# pyboard2.net
KiCad netlist of a schematic drawn in EAGLE
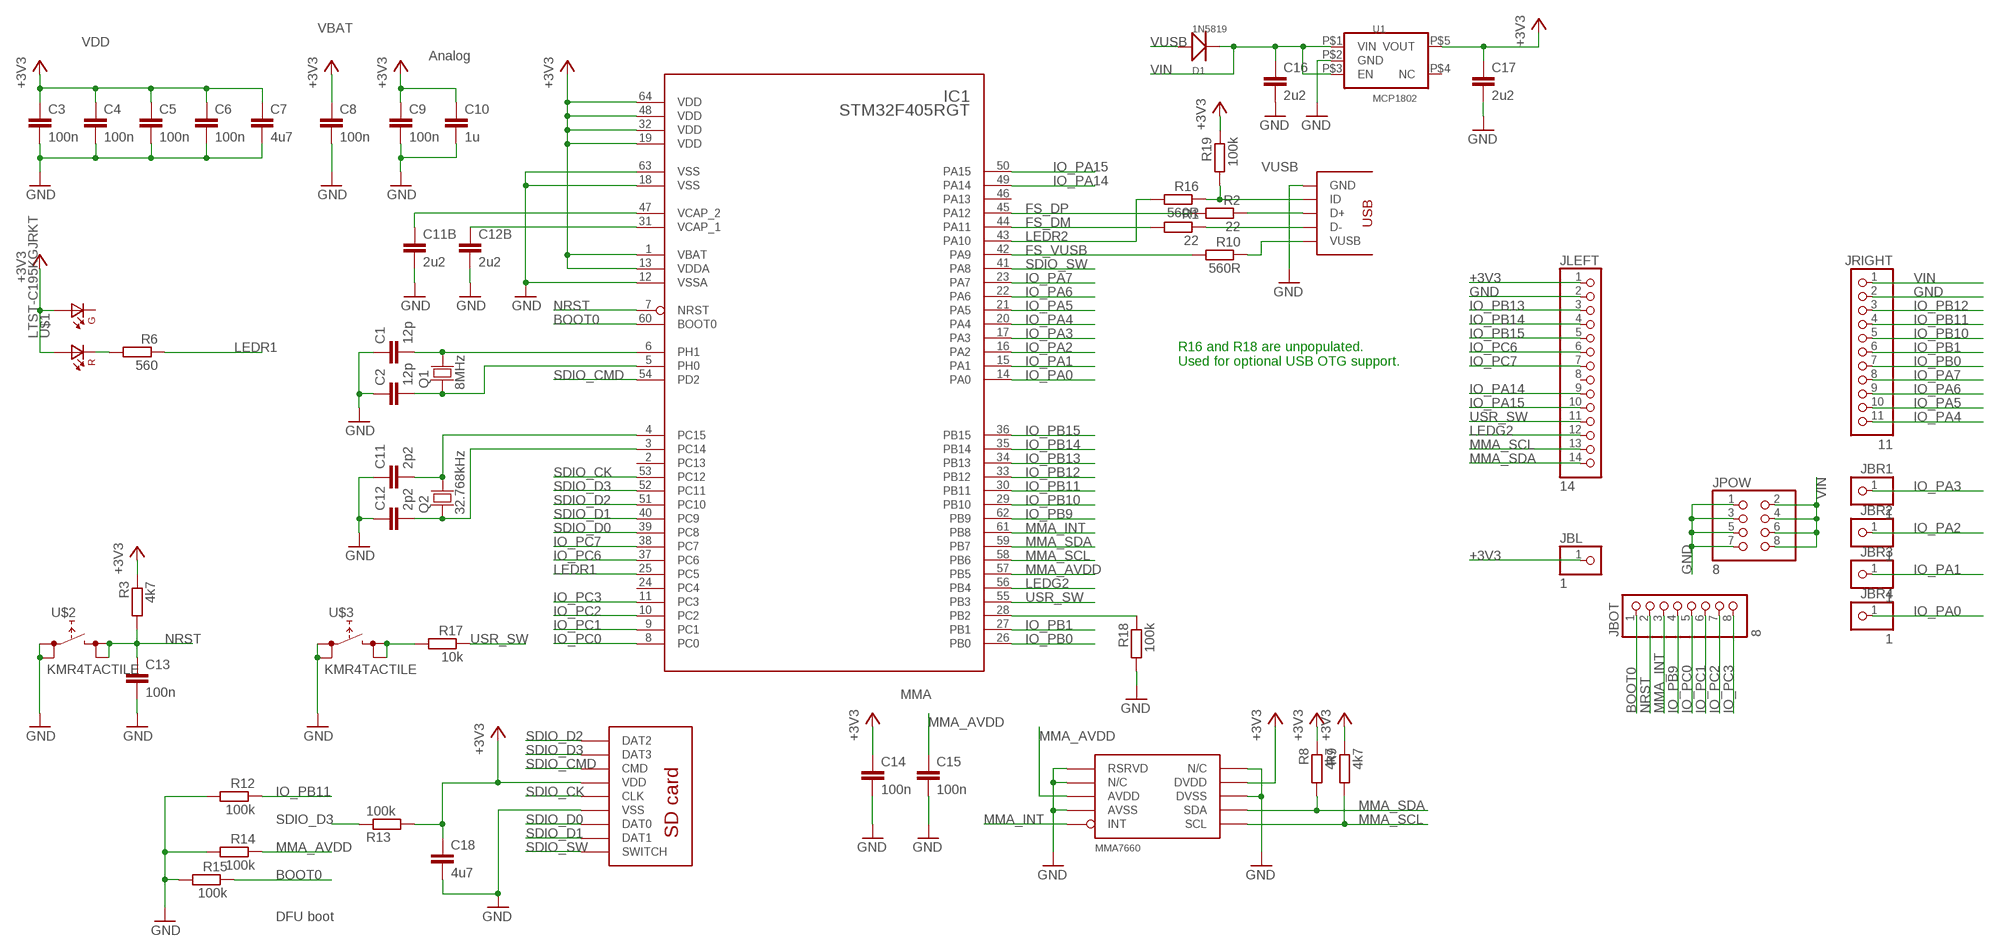
[diagram p0: schematic, sheet 1]

(export (version "E")
  (design (tool "Eeschema 10.0.6"))
  (components
    (comp (ref "C1")
      (value "12p")
      (footprint "eagle-import:C0603")
      (libsource (lib "eagle-import") (part "C-EUC0603"))
    )
    (comp (ref "C2")
      (value "12p")
      (footprint "eagle-import:C0603")
      (libsource (lib "eagle-import") (part "C-EUC0603"))
    )
    (comp (ref "C3")
      (value "100n")
      (footprint "eagle-import:C0603")
      (libsource (lib "eagle-import") (part "C-EUC0603"))
    )
    (comp (ref "C4")
      (value "100n")
      (footprint "eagle-import:C0603")
      (libsource (lib "eagle-import") (part "C-EUC0603"))
    )
    (comp (ref "C5")
      (value "100n")
      (footprint "eagle-import:C0603")
      (libsource (lib "eagle-import") (part "C-EUC0603"))
    )
    (comp (ref "C6")
      (value "100n")
      (footprint "eagle-import:C0603")
      (libsource (lib "eagle-import") (part "C-EUC0603"))
    )
    (comp (ref "C7")
      (value "4u7")
      (footprint "eagle-import:C0603")
      (libsource (lib "eagle-import") (part "C-EUC0603"))
    )
    (comp (ref "C8")
      (value "100n")
      (footprint "eagle-import:C0603")
      (libsource (lib "eagle-import") (part "C-EUC0603"))
    )
    (comp (ref "C9")
      (value "100n")
      (footprint "eagle-import:C0603")
      (libsource (lib "eagle-import") (part "C-EUC0603"))
    )
    (comp (ref "C10")
      (value "1u")
      (footprint "eagle-import:C0603")
      (libsource (lib "eagle-import") (part "C-EUC0603"))
    )
    (comp (ref "C11")
      (value "2p2")
      (footprint "eagle-import:C0603")
      (libsource (lib "eagle-import") (part "C-EUC0603"))
    )
    (comp (ref "C11B")
      (value "2u2")
      (footprint "eagle-import:C0603")
      (libsource (lib "eagle-import") (part "C-EUC0603"))
    )
    (comp (ref "C12")
      (value "2p2")
      (footprint "eagle-import:C0603")
      (libsource (lib "eagle-import") (part "C-EUC0603"))
    )
    (comp (ref "C12B")
      (value "2u2")
      (footprint "eagle-import:C0603")
      (libsource (lib "eagle-import") (part "C-EUC0603"))
    )
    (comp (ref "C13")
      (value "100n")
      (footprint "eagle-import:C0603")
      (libsource (lib "eagle-import") (part "C-EUC0603"))
    )
    (comp (ref "C14")
      (value "100n")
      (footprint "eagle-import:C0603")
      (libsource (lib "eagle-import") (part "C-EUC0603"))
    )
    (comp (ref "C15")
      (value "100n")
      (footprint "eagle-import:C0603")
      (libsource (lib "eagle-import") (part "C-EUC0603"))
    )
    (comp (ref "C16")
      (value "2u2")
      (footprint "eagle-import:C0603")
      (libsource (lib "eagle-import") (part "C-EUC0603"))
    )
    (comp (ref "C17")
      (value "2u2")
      (footprint "eagle-import:C0603")
      (libsource (lib "eagle-import") (part "C-EUC0603"))
    )
    (comp (ref "C18")
      (value "4u7")
      (footprint "eagle-import:C0603")
      (libsource (lib "eagle-import") (part "C-EUC0603"))
    )
    (comp (ref "D1")
      (value "1N5819")
      (footprint "eagle-import:SOD-123")
      (libsource (lib "eagle-import") (part "1N5819"))
    )
    (comp (ref "IC1")
      (value "STM32F405RGT")
      (footprint "eagle-import:LQFP64")
      (libsource (lib "eagle-import") (part "STM32F405RTG"))
    )
    (comp (ref "JBL")
      (value "1")
      (footprint "eagle-import:1X01")
      (libsource (lib "eagle-import") (part "PINHD-1X1"))
    )
    (comp (ref "JBOT")
      (value "8")
      (footprint "eagle-import:1X08")
      (libsource (lib "eagle-import") (part "PINHD-1X8"))
    )
    (comp (ref "JBR1")
      (value "1")
      (footprint "eagle-import:1X01")
      (libsource (lib "eagle-import") (part "PINHD-1X1"))
    )
    (comp (ref "JBR2")
      (value "1")
      (footprint "eagle-import:1X01")
      (libsource (lib "eagle-import") (part "PINHD-1X1"))
    )
    (comp (ref "JBR3")
      (value "1")
      (footprint "eagle-import:1X01")
      (libsource (lib "eagle-import") (part "PINHD-1X1"))
    )
    (comp (ref "JBR4")
      (value "1")
      (footprint "eagle-import:1X01")
      (libsource (lib "eagle-import") (part "PINHD-1X1"))
    )
    (comp (ref "JLEFT")
      (value "14")
      (footprint "eagle-import:1X14")
      (libsource (lib "eagle-import") (part "PINHD-1X14"))
    )
    (comp (ref "JPOW")
      (value "8")
      (footprint "eagle-import:2X04")
      (libsource (lib "eagle-import") (part "PINHD-2X4"))
    )
    (comp (ref "JRIGHT")
      (value "11")
      (footprint "eagle-import:1X11")
      (libsource (lib "eagle-import") (part "PINHD-1X11"))
    )
    (comp (ref "Q1")
      (value "8MHz")
      (footprint "eagle-import:TXC-SMD-50X32")
      (libsource (lib "eagle-import") (part "TXC-CRYSTAL50X32"))
    )
    (comp (ref "Q2")
      (value "32.768kHz")
      (footprint "eagle-import:TXC-SMD-32X15")
      (libsource (lib "eagle-import") (part "TXC-CRYSTAL32X15"))
    )
    (comp (ref "R1")
      (value "22")
      (footprint "eagle-import:R0603")
      (libsource (lib "eagle-import") (part "R-EU_R0603"))
    )
    (comp (ref "R2")
      (value "22")
      (footprint "eagle-import:R0603")
      (libsource (lib "eagle-import") (part "R-EU_R0603"))
    )
    (comp (ref "R3")
      (value "4k7")
      (footprint "eagle-import:R0603")
      (libsource (lib "eagle-import") (part "R-EU_R0603"))
    )
    (comp (ref "R6")
      (value "560")
      (footprint "eagle-import:R0603")
      (libsource (lib "eagle-import") (part "R-EU_R0603"))
    )
    (comp (ref "R8")
      (value "4k7")
      (footprint "eagle-import:R0603")
      (libsource (lib "eagle-import") (part "R-EU_R0603"))
    )
    (comp (ref "R9")
      (value "4k7")
      (footprint "eagle-import:R0603")
      (libsource (lib "eagle-import") (part "R-EU_R0603"))
    )
    (comp (ref "R10")
      (value "560R")
      (footprint "eagle-import:R0603")
      (libsource (lib "eagle-import") (part "R-EU_R0603"))
    )
    (comp (ref "R12")
      (value "100k")
      (footprint "eagle-import:R0603")
      (libsource (lib "eagle-import") (part "R-EU_R0603"))
    )
    (comp (ref "R13")
      (value "100k")
      (footprint "eagle-import:R0603")
      (libsource (lib "eagle-import") (part "R-EU_R0603"))
    )
    (comp (ref "R14")
      (value "100k")
      (footprint "eagle-import:R0603")
      (libsource (lib "eagle-import") (part "R-EU_R0603"))
    )
    (comp (ref "R15")
      (value "100k")
      (footprint "eagle-import:R0603")
      (libsource (lib "eagle-import") (part "R-EU_R0603"))
    )
    (comp (ref "R16")
      (value "560R")
      (footprint "eagle-import:R0603")
      (libsource (lib "eagle-import") (part "R-EU_R0603"))
    )
    (comp (ref "R17")
      (value "10k")
      (footprint "eagle-import:R0603")
      (libsource (lib "eagle-import") (part "R-EU_R0603"))
    )
    (comp (ref "R18")
      (value "100k")
      (footprint "eagle-import:R0603")
      (libsource (lib "eagle-import") (part "R-EU_R0603"))
    )
    (comp (ref "R19")
      (value "100k")
      (footprint "eagle-import:R0603")
      (libsource (lib "eagle-import") (part "R-EU_R0603"))
    )
    (comp (ref "U$1")
      (value "LTST-C195KGJRKT")
      (footprint "eagle-import:LTST-BILED-15X16")
      (libsource (lib "eagle-import") (part "LTST-C195KGJRKT"))
    )
    (comp (ref "U$2")
      (value "KMR4TACTILE")
      (footprint "eagle-import:KMR4SWITCH")
      (libsource (lib "eagle-import") (part "KMR4TACTILE"))
    )
    (comp (ref "U$3")
      (value "KMR4TACTILE")
      (footprint "eagle-import:KMR4SWITCH")
      (libsource (lib "eagle-import") (part "KMR4TACTILE"))
    )
    (comp (ref "U$4")
      (value "MOLEX-SD-105027")
      (footprint "eagle-import:MOLEX-SD-105027-PKG")
      (libsource (lib "eagle-import") (part "MOLEX-SD-105027"))
    )
    (comp (ref "U$5")
      (value "MMA7660")
      (footprint "eagle-import:DFN10")
      (libsource (lib "eagle-import") (part "MMA7660"))
    )
    (comp (ref "U$7")
      (value "USB-MICRO-AB")
      (footprint "eagle-import:HRS-USB-ZX62D-AB-5P8-PKG")
      (libsource (lib "eagle-import") (part "USB-MICRO-AB"))
    )
    (comp (ref "U1")
      (value "MCP1802")
      (footprint "eagle-import:SOT-23-5")
      (libsource (lib "eagle-import") (part "MCP1802"))
    )
  )
  (nets
    (net (code "1") (name "+3V3") (class "Default")
      (node (ref "C10") (pin "1") (pinfunction "1_1") (pintype "passive"))
      (node (ref "C14") (pin "1") (pinfunction "1_1") (pintype "passive"))
      (node (ref "C17") (pin "1") (pinfunction "1_1") (pintype "passive"))
      (node (ref "C18") (pin "1") (pinfunction "1_1") (pintype "passive"))
      (node (ref "C3") (pin "1") (pinfunction "1_1") (pintype "passive"))
      (node (ref "C4") (pin "1") (pinfunction "1_1") (pintype "passive"))
      (node (ref "C5") (pin "1") (pinfunction "1_1") (pintype "passive"))
      (node (ref "C6") (pin "1") (pinfunction "1_1") (pintype "passive"))
      (node (ref "C7") (pin "1") (pinfunction "1_1") (pintype "passive"))
      (node (ref "C8") (pin "1") (pinfunction "1_1") (pintype "passive"))
      (node (ref "C9") (pin "1") (pinfunction "1_1") (pintype "passive"))
      (node (ref "IC1") (pin "1") (pinfunction "VBAT_1") (pintype "power_in"))
      (node (ref "IC1") (pin "13") (pinfunction "VDDA_13") (pintype "power_in"))
      (node (ref "IC1") (pin "19") (pinfunction "VDD_19") (pintype "power_in"))
      (node (ref "IC1") (pin "32") (pinfunction "VDD_32") (pintype "power_in"))
      (node (ref "IC1") (pin "48") (pinfunction "VDD_48") (pintype "power_in"))
      (node (ref "IC1") (pin "64") (pinfunction "VDD_64") (pintype "power_in"))
      (node (ref "JBL") (pin "1") (pinfunction "1_1") (pintype "passive"))
      (node (ref "JLEFT") (pin "1") (pinfunction "1_1") (pintype "passive"))
      (node (ref "R13") (pin "2") (pinfunction "2_2") (pintype "passive"))
      (node (ref "R19") (pin "1") (pinfunction "1_1") (pintype "passive"))
      (node (ref "R3") (pin "1") (pinfunction "1_1") (pintype "passive"))
      (node (ref "R8") (pin "1") (pinfunction "1_1") (pintype "passive"))
      (node (ref "R9") (pin "1") (pinfunction "1_1") (pintype "passive"))
      (node (ref "U$1") (pin "P$1") (pinfunction "A1_P$1") (pintype "passive"))
      (node (ref "U$1") (pin "P$2") (pinfunction "A2_P$2") (pintype "passive"))
      (node (ref "U$4") (pin "P$4") (pinfunction "VDD_P$4") (pintype "bidirectional"))
      (node (ref "U$5") (pin "P$9") (pinfunction "DVDD_P$9") (pintype "power_in"))
      (node (ref "U1") (pin "P$5") (pinfunction "VOUT_P$5") (pintype "power_in"))
    )
    (net (code "2") (name "/BOOT0") (class "Default")
      (node (ref "IC1") (pin "60") (pinfunction "BOOT0_60") (pintype "bidirectional"))
      (node (ref "JBOT") (pin "1") (pinfunction "1_1") (pintype "passive"))
      (node (ref "R15") (pin "1") (pinfunction "1_1") (pintype "passive"))
    )
    (net (code "3") (name "/FS_DM") (class "Default")
      (node (ref "IC1") (pin "44") (pinfunction "PA11_44") (pintype "bidirectional"))
      (node (ref "R1") (pin "2") (pinfunction "2_2") (pintype "passive"))
    )
    (net (code "4") (name "/FS_DP") (class "Default")
      (node (ref "IC1") (pin "45") (pinfunction "PA12_45") (pintype "bidirectional"))
      (node (ref "R2") (pin "2") (pinfunction "2_2") (pintype "passive"))
    )
    (net (code "5") (name "/FS_VUSB") (class "Default")
      (node (ref "IC1") (pin "42") (pinfunction "PA9_42") (pintype "bidirectional"))
      (node (ref "R10") (pin "2") (pinfunction "2_2") (pintype "passive"))
    )
    (net (code "6") (name "/IO_PA0") (class "Default")
      (node (ref "IC1") (pin "14") (pinfunction "PA0_14") (pintype "bidirectional"))
      (node (ref "JBR4") (pin "1") (pinfunction "1_1") (pintype "passive"))
    )
    (net (code "7") (name "/IO_PA1") (class "Default")
      (node (ref "IC1") (pin "15") (pinfunction "PA1_15") (pintype "bidirectional"))
      (node (ref "JBR3") (pin "1") (pinfunction "1_1") (pintype "passive"))
    )
    (net (code "8") (name "/IO_PA2") (class "Default")
      (node (ref "IC1") (pin "16") (pinfunction "PA2_16") (pintype "bidirectional"))
      (node (ref "JBR2") (pin "1") (pinfunction "1_1") (pintype "passive"))
    )
    (net (code "9") (name "/IO_PA3") (class "Default")
      (node (ref "IC1") (pin "17") (pinfunction "PA3_17") (pintype "bidirectional"))
      (node (ref "JBR1") (pin "1") (pinfunction "1_1") (pintype "passive"))
    )
    (net (code "10") (name "/IO_PA4") (class "Default")
      (node (ref "IC1") (pin "20") (pinfunction "PA4_20") (pintype "bidirectional"))
      (node (ref "JRIGHT") (pin "11") (pinfunction "11_11") (pintype "passive"))
    )
    (net (code "11") (name "/IO_PA5") (class "Default")
      (node (ref "IC1") (pin "21") (pinfunction "PA5_21") (pintype "bidirectional"))
      (node (ref "JRIGHT") (pin "10") (pinfunction "10_10") (pintype "passive"))
    )
    (net (code "12") (name "/IO_PA6") (class "Default")
      (node (ref "IC1") (pin "22") (pinfunction "PA6_22") (pintype "bidirectional"))
      (node (ref "JRIGHT") (pin "9") (pinfunction "9_9") (pintype "passive"))
    )
    (net (code "13") (name "/IO_PA7") (class "Default")
      (node (ref "IC1") (pin "23") (pinfunction "PA7_23") (pintype "bidirectional"))
      (node (ref "JRIGHT") (pin "8") (pinfunction "8_8") (pintype "passive"))
    )
    (net (code "14") (name "/IO_PA14") (class "Default")
      (node (ref "IC1") (pin "49") (pinfunction "PA14_49") (pintype "bidirectional"))
      (node (ref "JLEFT") (pin "9") (pinfunction "9_9") (pintype "passive"))
    )
    (net (code "15") (name "/IO_PA15") (class "Default")
      (node (ref "IC1") (pin "50") (pinfunction "PA15_50") (pintype "bidirectional"))
      (node (ref "JLEFT") (pin "10") (pinfunction "10_10") (pintype "passive"))
    )
    (net (code "16") (name "/IO_PB0") (class "Default")
      (node (ref "IC1") (pin "26") (pinfunction "PB0_26") (pintype "bidirectional"))
      (node (ref "JRIGHT") (pin "7") (pinfunction "7_7") (pintype "passive"))
    )
    (net (code "17") (name "/IO_PB1") (class "Default")
      (node (ref "IC1") (pin "27") (pinfunction "PB1_27") (pintype "bidirectional"))
      (node (ref "JRIGHT") (pin "6") (pinfunction "6_6") (pintype "passive"))
    )
    (net (code "18") (name "/IO_PB9") (class "Default")
      (node (ref "IC1") (pin "62") (pinfunction "PB9_62") (pintype "bidirectional"))
      (node (ref "JBOT") (pin "4") (pinfunction "4_4") (pintype "passive"))
    )
    (net (code "19") (name "/IO_PB10") (class "Default")
      (node (ref "IC1") (pin "29") (pinfunction "PB10_29") (pintype "bidirectional"))
      (node (ref "JRIGHT") (pin "5") (pinfunction "5_5") (pintype "passive"))
    )
    (net (code "20") (name "/IO_PB11") (class "Default")
      (node (ref "IC1") (pin "30") (pinfunction "PB11_30") (pintype "bidirectional"))
      (node (ref "JRIGHT") (pin "4") (pinfunction "4_4") (pintype "passive"))
      (node (ref "R12") (pin "1") (pinfunction "1_1") (pintype "passive"))
    )
    (net (code "21") (name "/IO_PB12") (class "Default")
      (node (ref "IC1") (pin "33") (pinfunction "PB12_33") (pintype "bidirectional"))
      (node (ref "JRIGHT") (pin "3") (pinfunction "3_3") (pintype "passive"))
    )
    (net (code "22") (name "/IO_PB13") (class "Default")
      (node (ref "IC1") (pin "34") (pinfunction "PB13_34") (pintype "bidirectional"))
      (node (ref "JLEFT") (pin "3") (pinfunction "3_3") (pintype "passive"))
    )
    (net (code "23") (name "/IO_PB14") (class "Default")
      (node (ref "IC1") (pin "35") (pinfunction "PB14_35") (pintype "bidirectional"))
      (node (ref "JLEFT") (pin "4") (pinfunction "4_4") (pintype "passive"))
    )
    (net (code "24") (name "/IO_PB15") (class "Default")
      (node (ref "IC1") (pin "36") (pinfunction "PB15_36") (pintype "bidirectional"))
      (node (ref "JLEFT") (pin "5") (pinfunction "5_5") (pintype "passive"))
    )
    (net (code "25") (name "/IO_PC0") (class "Default")
      (node (ref "IC1") (pin "8") (pinfunction "PC0_8") (pintype "bidirectional"))
      (node (ref "JBOT") (pin "5") (pinfunction "5_5") (pintype "passive"))
    )
    (net (code "26") (name "/IO_PC1") (class "Default")
      (node (ref "IC1") (pin "9") (pinfunction "PC1_9") (pintype "bidirectional"))
      (node (ref "JBOT") (pin "6") (pinfunction "6_6") (pintype "passive"))
    )
    (net (code "27") (name "/IO_PC2") (class "Default")
      (node (ref "IC1") (pin "10") (pinfunction "PC2_10") (pintype "bidirectional"))
      (node (ref "JBOT") (pin "7") (pinfunction "7_7") (pintype "passive"))
    )
    (net (code "28") (name "/IO_PC3") (class "Default")
      (node (ref "IC1") (pin "11") (pinfunction "PC3_11") (pintype "bidirectional"))
      (node (ref "JBOT") (pin "8") (pinfunction "8_8") (pintype "passive"))
    )
    (net (code "29") (name "/IO_PC6") (class "Default")
      (node (ref "IC1") (pin "37") (pinfunction "PC6_37") (pintype "bidirectional"))
      (node (ref "JLEFT") (pin "6") (pinfunction "6_6") (pintype "passive"))
    )
    (net (code "30") (name "/IO_PC7") (class "Default")
      (node (ref "IC1") (pin "38") (pinfunction "PC7_38") (pintype "bidirectional"))
      (node (ref "JLEFT") (pin "7") (pinfunction "7_7") (pintype "passive"))
    )
    (net (code "31") (name "/LEDG2") (class "Default")
      (node (ref "IC1") (pin "56") (pinfunction "PB4_56") (pintype "bidirectional"))
      (node (ref "JLEFT") (pin "12") (pinfunction "12_12") (pintype "passive"))
    )
    (net (code "32") (name "/LEDR1") (class "Default")
      (node (ref "IC1") (pin "25") (pinfunction "PC5_25") (pintype "bidirectional"))
      (node (ref "R6") (pin "1") (pinfunction "1_1") (pintype "passive"))
    )
    (net (code "33") (name "/LEDR2") (class "Default")
      (node (ref "IC1") (pin "43") (pinfunction "PA10_43") (pintype "bidirectional"))
      (node (ref "R16") (pin "2") (pinfunction "2_2") (pintype "passive"))
    )
    (net (code "34") (name "/MMA_AVDD") (class "Default")
      (node (ref "C15") (pin "1") (pinfunction "1_1") (pintype "passive"))
      (node (ref "IC1") (pin "57") (pinfunction "PB5_57") (pintype "bidirectional"))
      (node (ref "R14") (pin "1") (pinfunction "1_1") (pintype "passive"))
      (node (ref "U$5") (pin "P$3") (pinfunction "AVDD_P$3") (pintype "power_in"))
    )
    (net (code "35") (name "/MMA_INT") (class "Default")
      (node (ref "IC1") (pin "61") (pinfunction "PB8_61") (pintype "bidirectional"))
      (node (ref "JBOT") (pin "3") (pinfunction "3_3") (pintype "passive"))
      (node (ref "U$5") (pin "P$5") (pinfunction "INT_P$5") (pintype "output"))
    )
    (net (code "36") (name "/MMA_SCL") (class "Default")
      (node (ref "IC1") (pin "58") (pinfunction "PB6_58") (pintype "bidirectional"))
      (node (ref "JLEFT") (pin "13") (pinfunction "13_13") (pintype "passive"))
      (node (ref "R9") (pin "2") (pinfunction "2_2") (pintype "passive"))
      (node (ref "U$5") (pin "P$6") (pinfunction "SCL_P$6") (pintype "input"))
    )
    (net (code "37") (name "/MMA_SDA") (class "Default")
      (node (ref "IC1") (pin "59") (pinfunction "PB7_59") (pintype "bidirectional"))
      (node (ref "JLEFT") (pin "14") (pinfunction "14_14") (pintype "passive"))
      (node (ref "R8") (pin "2") (pinfunction "2_2") (pintype "passive"))
      (node (ref "U$5") (pin "P$7") (pinfunction "SDA_P$7") (pintype "output"))
    )
    (net (code "38") (name "/NRST") (class "Default")
      (node (ref "C13") (pin "1") (pinfunction "1_1") (pintype "passive"))
      (node (ref "IC1") (pin "7") (pinfunction "NRST_7") (pintype "input"))
      (node (ref "JBOT") (pin "2") (pinfunction "2_2") (pintype "passive"))
      (node (ref "R3") (pin "2") (pinfunction "2_2") (pintype "passive"))
      (node (ref "U$2") (pin "P$3") (pinfunction "1_P$3") (pintype "passive"))
      (node (ref "U$2") (pin "P$4") (pinfunction "1_P$4") (pintype "passive"))
    )
    (net (code "39") (name "/SDIO_CK") (class "Default")
      (node (ref "IC1") (pin "53") (pinfunction "PC12_53") (pintype "bidirectional"))
      (node (ref "U$4") (pin "P$5") (pinfunction "CLK_P$5") (pintype "bidirectional"))
    )
    (net (code "40") (name "/SDIO_CMD") (class "Default")
      (node (ref "IC1") (pin "54") (pinfunction "PD2_54") (pintype "bidirectional"))
      (node (ref "U$4") (pin "P$3") (pinfunction "CMD_P$3") (pintype "bidirectional"))
    )
    (net (code "41") (name "/SDIO_D0") (class "Default")
      (node (ref "IC1") (pin "39") (pinfunction "PC8_39") (pintype "bidirectional"))
      (node (ref "U$4") (pin "P$7") (pinfunction "DAT0_P$7") (pintype "bidirectional"))
    )
    (net (code "42") (name "/SDIO_D1") (class "Default")
      (node (ref "IC1") (pin "40") (pinfunction "PC9_40") (pintype "bidirectional"))
      (node (ref "U$4") (pin "P$8") (pinfunction "DAT1_P$8") (pintype "bidirectional"))
    )
    (net (code "43") (name "/SDIO_D2") (class "Default")
      (node (ref "IC1") (pin "51") (pinfunction "PC10_51") (pintype "bidirectional"))
      (node (ref "U$4") (pin "P$1") (pinfunction "DAT2_P$1") (pintype "bidirectional"))
    )
    (net (code "44") (name "/SDIO_D3") (class "Default")
      (node (ref "IC1") (pin "52") (pinfunction "PC11_52") (pintype "bidirectional"))
      (node (ref "R13") (pin "1") (pinfunction "1_1") (pintype "passive"))
      (node (ref "U$4") (pin "P$2") (pinfunction "DAT3_P$2") (pintype "bidirectional"))
    )
    (net (code "45") (name "/SDIO_SW") (class "Default")
      (node (ref "IC1") (pin "41") (pinfunction "PA8_41") (pintype "bidirectional"))
      (node (ref "U$4") (pin "G$1") (pinfunction "SWITCH_G$1") (pintype "bidirectional"))
    )
    (net (code "46") (name "/USR_SW") (class "Default")
      (node (ref "IC1") (pin "55") (pinfunction "PB3_55") (pintype "bidirectional"))
      (node (ref "JLEFT") (pin "11") (pinfunction "11_11") (pintype "passive"))
      (node (ref "R17") (pin "1") (pinfunction "1_1") (pintype "passive"))
    )
    (net (code "47") (name "/VIN") (class "Default")
      (node (ref "C16") (pin "1") (pinfunction "1_1") (pintype "passive"))
      (node (ref "D1") (pin "K") (pinfunction "K_K") (pintype "passive"))
      (node (ref "JPOW") (pin "2") (pinfunction "2_2") (pintype "passive"))
      (node (ref "JPOW") (pin "4") (pinfunction "4_4") (pintype "passive"))
      (node (ref "JPOW") (pin "6") (pinfunction "6_6") (pintype "passive"))
      (node (ref "JPOW") (pin "8") (pinfunction "8_8") (pintype "passive"))
      (node (ref "JRIGHT") (pin "1") (pinfunction "1_1") (pintype "passive"))
      (node (ref "U1") (pin "P$1") (pinfunction "VIN_P$1") (pintype "power_in"))
      (node (ref "U1") (pin "P$3") (pinfunction "EN_P$3") (pintype "input"))
    )
    (net (code "48") (name "/VUSB") (class "Default")
      (node (ref "D1") (pin "A") (pinfunction "A_A") (pintype "passive"))
      (node (ref "R10") (pin "1") (pinfunction "1_1") (pintype "passive"))
      (node (ref "U$7") (pin "P$1") (pinfunction "VUSB_P$1") (pintype "power_in"))
    )
    (net (code "49") (name "GND") (class "Default")
      (node (ref "C1") (pin "1") (pinfunction "1_1") (pintype "passive"))
      (node (ref "C10") (pin "2") (pinfunction "2_2") (pintype "passive"))
      (node (ref "C11") (pin "1") (pinfunction "1_1") (pintype "passive"))
      (node (ref "C11B") (pin "2") (pinfunction "2_2") (pintype "passive"))
      (node (ref "C12") (pin "1") (pinfunction "1_1") (pintype "passive"))
      (node (ref "C12B") (pin "2") (pinfunction "2_2") (pintype "passive"))
      (node (ref "C13") (pin "2") (pinfunction "2_2") (pintype "passive"))
      (node (ref "C14") (pin "2") (pinfunction "2_2") (pintype "passive"))
      (node (ref "C15") (pin "2") (pinfunction "2_2") (pintype "passive"))
      (node (ref "C16") (pin "2") (pinfunction "2_2") (pintype "passive"))
      (node (ref "C17") (pin "2") (pinfunction "2_2") (pintype "passive"))
      (node (ref "C18") (pin "2") (pinfunction "2_2") (pintype "passive"))
      (node (ref "C2") (pin "1") (pinfunction "1_1") (pintype "passive"))
      (node (ref "C3") (pin "2") (pinfunction "2_2") (pintype "passive"))
      (node (ref "C4") (pin "2") (pinfunction "2_2") (pintype "passive"))
      (node (ref "C5") (pin "2") (pinfunction "2_2") (pintype "passive"))
      (node (ref "C6") (pin "2") (pinfunction "2_2") (pintype "passive"))
      (node (ref "C7") (pin "2") (pinfunction "2_2") (pintype "passive"))
      (node (ref "C8") (pin "2") (pinfunction "2_2") (pintype "passive"))
      (node (ref "C9") (pin "2") (pinfunction "2_2") (pintype "passive"))
      (node (ref "IC1") (pin "12") (pinfunction "VSSA_12") (pintype "power_in"))
      (node (ref "IC1") (pin "18") (pinfunction "VSS_18") (pintype "power_in"))
      (node (ref "IC1") (pin "63") (pinfunction "VSS_63") (pintype "power_in"))
      (node (ref "JLEFT") (pin "2") (pinfunction "2_2") (pintype "passive"))
      (node (ref "JPOW") (pin "1") (pinfunction "1_1") (pintype "passive"))
      (node (ref "JPOW") (pin "3") (pinfunction "3_3") (pintype "passive"))
      (node (ref "JPOW") (pin "5") (pinfunction "5_5") (pintype "passive"))
      (node (ref "JPOW") (pin "7") (pinfunction "7_7") (pintype "passive"))
      (node (ref "JRIGHT") (pin "2") (pinfunction "2_2") (pintype "passive"))
      (node (ref "R12") (pin "2") (pinfunction "2_2") (pintype "passive"))
      (node (ref "R14") (pin "2") (pinfunction "2_2") (pintype "passive"))
      (node (ref "R15") (pin "2") (pinfunction "2_2") (pintype "passive"))
      (node (ref "R18") (pin "2") (pinfunction "2_2") (pintype "passive"))
      (node (ref "U$2") (pin "P$1") (pinfunction "0_P$1") (pintype "passive"))
      (node (ref "U$2") (pin "P$2") (pinfunction "0_P$2") (pintype "passive"))
      (node (ref "U$3") (pin "P$1") (pinfunction "0_P$1") (pintype "passive"))
      (node (ref "U$3") (pin "P$2") (pinfunction "0_P$2") (pintype "passive"))
      (node (ref "U$4") (pin "P$6") (pinfunction "VSS_P$6") (pintype "bidirectional"))
      (node (ref "U$5") (pin "P$1") (pinfunction "RSRVD_P$1") (pintype "input"))
      (node (ref "U$5") (pin "P$10") (pinfunction "N/C_P$10") (pintype "input"))
      (node (ref "U$5") (pin "P$2") (pinfunction "N/C_P$2") (pintype "input"))
      (node (ref "U$5") (pin "P$4") (pinfunction "AVSS_P$4") (pintype "power_in"))
      (node (ref "U$5") (pin "P$8") (pinfunction "DVSS_P$8") (pintype "power_in"))
      (node (ref "U$7") (pin "P$5") (pinfunction "GND_P$5") (pintype "power_in"))
      (node (ref "U1") (pin "P$2") (pinfunction "GND_P$2") (pintype "power_in"))
    )
    (net (code "50") (name "Net-(IC1-PB2)") (class "Default")
      (node (ref "IC1") (pin "28") (pinfunction "PB2_28") (pintype "bidirectional"))
      (node (ref "R18") (pin "1") (pinfunction "1_1") (pintype "passive"))
    )
    (net (code "51") (name "Net-(IC1-PC14)") (class "Default")
      (node (ref "C12") (pin "2") (pinfunction "2_2") (pintype "passive"))
      (node (ref "IC1") (pin "3") (pinfunction "PC14_3") (pintype "bidirectional"))
      (node (ref "Q2") (pin "P$1") (pinfunction "P$1_P$1") (pintype "passive"))
    )
    (net (code "52") (name "Net-(IC1-PC15)") (class "Default")
      (node (ref "C11") (pin "2") (pinfunction "2_2") (pintype "passive"))
      (node (ref "IC1") (pin "4") (pinfunction "PC15_4") (pintype "bidirectional"))
      (node (ref "Q2") (pin "P$2") (pinfunction "P$2_P$2") (pintype "passive"))
    )
    (net (code "53") (name "Net-(IC1-PH0)") (class "Default")
      (node (ref "C2") (pin "2") (pinfunction "2_2") (pintype "passive"))
      (node (ref "IC1") (pin "5") (pinfunction "PH0_5") (pintype "bidirectional"))
      (node (ref "Q1") (pin "P$1") (pinfunction "P$1_P$1") (pintype "passive"))
    )
    (net (code "54") (name "Net-(IC1-PH1)") (class "Default")
      (node (ref "C1") (pin "2") (pinfunction "2_2") (pintype "passive"))
      (node (ref "IC1") (pin "6") (pinfunction "PH1_6") (pintype "bidirectional"))
      (node (ref "Q1") (pin "P$2") (pinfunction "P$2_P$2") (pintype "passive"))
    )
    (net (code "55") (name "Net-(IC1-VCAP_1)") (class "Default")
      (node (ref "C12B") (pin "1") (pinfunction "1_1") (pintype "passive"))
      (node (ref "IC1") (pin "31") (pinfunction "VCAP_1_31") (pintype "passive"))
    )
    (net (code "56") (name "Net-(IC1-VCAP_2)") (class "Default")
      (node (ref "C11B") (pin "1") (pinfunction "1_1") (pintype "passive"))
      (node (ref "IC1") (pin "47") (pinfunction "VCAP_2_47") (pintype "passive"))
    )
    (net (code "57") (name "Net-(R17-Pad2)") (class "Default")
      (node (ref "R17") (pin "2") (pinfunction "2_2") (pintype "passive"))
      (node (ref "U$3") (pin "P$3") (pinfunction "1_P$3") (pintype "passive"))
      (node (ref "U$3") (pin "P$4") (pinfunction "1_P$4") (pintype "passive"))
    )
    (net (code "58") (name "Net-(U$1-K2)") (class "Default")
      (node (ref "R6") (pin "2") (pinfunction "2_2") (pintype "passive"))
      (node (ref "U$1") (pin "P$4") (pinfunction "K2_P$4") (pintype "passive"))
    )
    (net (code "59") (name "Net-(U$7-D+)") (class "Default")
      (node (ref "R2") (pin "1") (pinfunction "1_1") (pintype "passive"))
      (node (ref "U$7") (pin "P$3") (pinfunction "D+_P$3") (pintype "bidirectional"))
    )
    (net (code "60") (name "Net-(U$7-D-)") (class "Default")
      (node (ref "R1") (pin "1") (pinfunction "1_1") (pintype "passive"))
      (node (ref "U$7") (pin "P$2") (pinfunction "D-_P$2") (pintype "bidirectional"))
    )
    (net (code "61") (name "Net-(U$7-ID)") (class "Default")
      (node (ref "R16") (pin "1") (pinfunction "1_1") (pintype "passive"))
      (node (ref "R19") (pin "2") (pinfunction "2_2") (pintype "passive"))
      (node (ref "U$7") (pin "P$4") (pinfunction "ID_P$4") (pintype "bidirectional"))
    )
    (net (code "62") (name "unconnected-(IC1-PA13-Pad46)") (class "Default")
      (node (ref "IC1") (pin "46") (pinfunction "PA13_46") (pintype "bidirectional"))
    )
    (net (code "63") (name "unconnected-(IC1-PC4-Pad24)") (class "Default")
      (node (ref "IC1") (pin "24") (pinfunction "PC4_24") (pintype "bidirectional"))
    )
    (net (code "64") (name "unconnected-(IC1-PC13-Pad2)") (class "Default")
      (node (ref "IC1") (pin "2") (pinfunction "PC13_2") (pintype "bidirectional"))
    )
    (net (code "65") (name "unconnected-(JLEFT-Pad8)") (class "Default")
      (node (ref "JLEFT") (pin "8") (pinfunction "8_8") (pintype "passive"))
    )
    (net (code "66") (name "unconnected-(U$1-K1-PadP$3)") (class "Default")
      (node (ref "U$1") (pin "P$3") (pinfunction "K1_P$3") (pintype "passive"))
    )
    (net (code "67") (name "unconnected-(U1-NC-PadP$4)") (class "Default")
      (node (ref "U1") (pin "P$4") (pinfunction "NC_P$4") (pintype "no_connect"))
    )
  )
)
